# external_MCU.net
KiCad netlist of a schematic drawn in Altium Designer
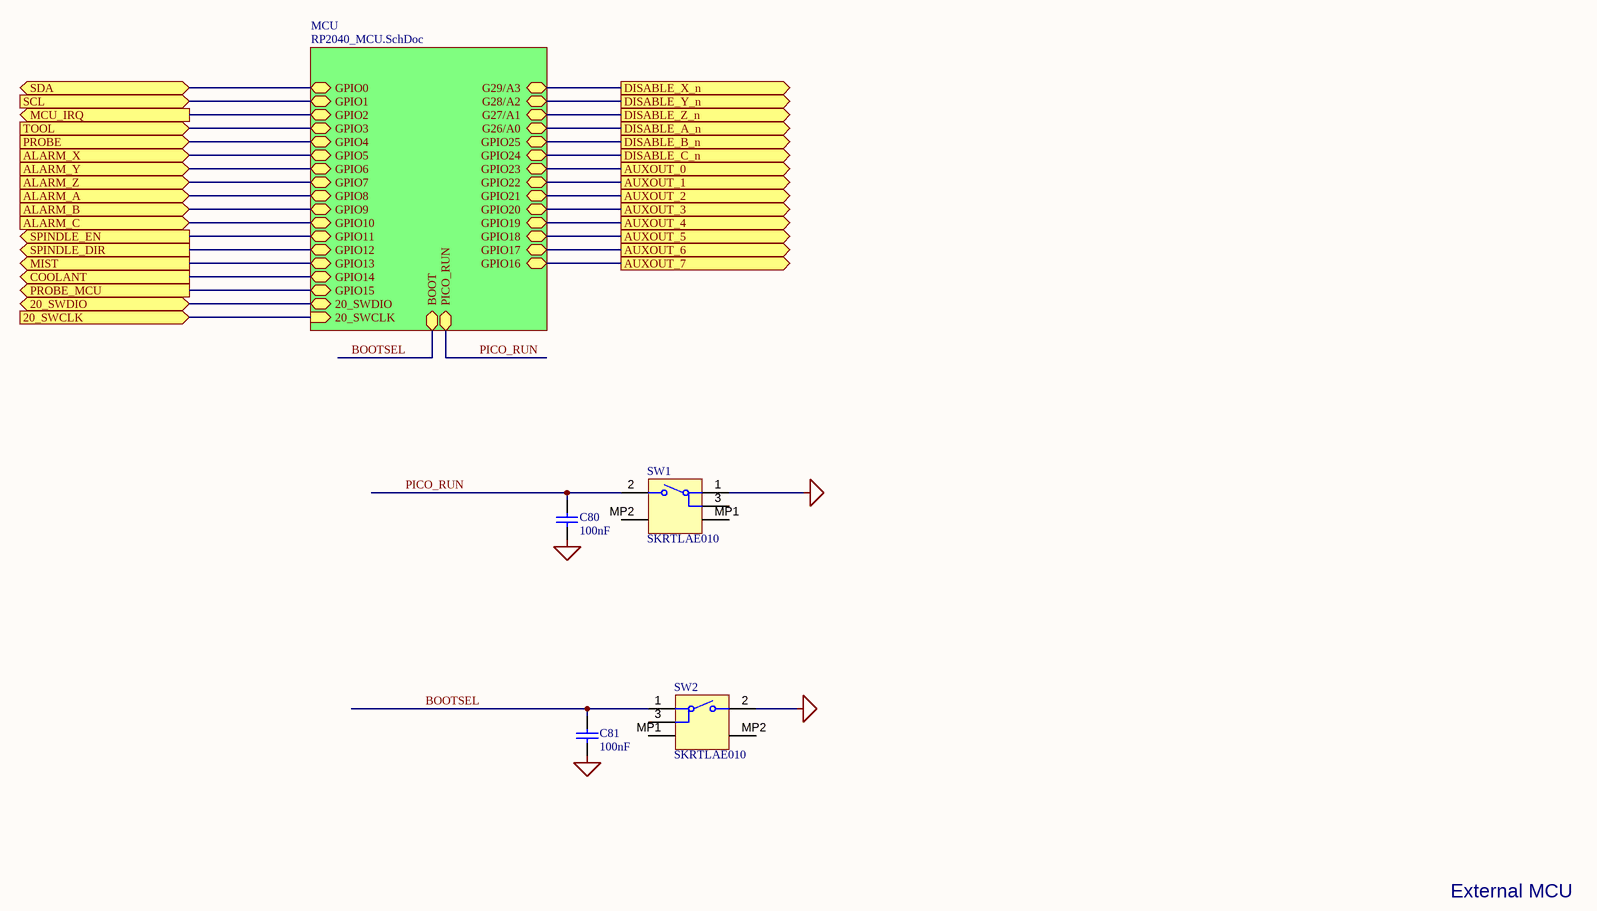
[diagram p0: external_MCU.SchDoc]

(export (version "E")
  (design (tool "Eeschema 10.0.6"))
  (components
    (comp (ref "C80")
      (value "100nF")
      (footprint "0402_C")
      (description "Chip capacitors")
      (fields
        (field (name "MANUFACTURER") "Samsung Electro-Mechanics")
        (field (name "PARTNUMBER") "CL05B104KO5NNNC")
      )
      (libsource (lib "Cap") (part "0402 100nF (104) 10% 16V"))
    )
    (comp (ref "C81")
      (value "100nF")
      (footprint "0402_C")
      (description "Chip capacitors")
      (fields
        (field (name "MANUFACTURER") "Samsung Electro-Mechanics")
        (field (name "PARTNUMBER") "CL05B104KO5NNNC")
      )
      (libsource (lib "Cap") (part "0402 100nF (104) 10% 16V"))
    )
    (comp (ref "SW1")
      (value "SKRTLAE010")
      (footprint "ALPS-SKRTLAE010_V")
      (description "Side Push Type, 250 V, -40 to 90 degC, 3-Pin SMD, RoHS, Tape and Reel")
      (fields (field (name "MANUFACTURER") "ALPS"))
      (libsource (lib "") (part "SW_SPST-3_A_1"))
    )
    (comp (ref "SW2")
      (value "SKRTLAE010")
      (footprint "ALPS-SKRTLAE010_V")
      (description "Side Push Type, 250 V, -40 to 90 degC, 3-Pin SMD, RoHS, Tape and Reel")
      (fields (field (name "MANUFACTURER") "ALPS"))
      (libsource (lib "Altium Content Vault") (part "SW_SPST-3_A"))
    )
  )
  (nets
    (net (code "17") (name "/BOOTSEL") (class "Default")
      (node (ref "C81") (pin "2") (pinfunction "2_2") (pintype "passive"))
      (node (ref "SW2") (pin "1") (pinfunction "1_1") (pintype "passive"))
    )
    (net (code "27") (name "/PICO_RUN") (class "Default")
      (node (ref "C80") (pin "2") (pinfunction "2_2") (pintype "passive"))
      (node (ref "SW1") (pin "2") (pinfunction "2_2") (pintype "passive"))
    )
    (net (code "35") (name "MCU_GND") (class "Default")
      (node (ref "C80") (pin "1") (pinfunction "1_1") (pintype "passive"))
      (node (ref "C81") (pin "1") (pinfunction "1_1") (pintype "passive"))
      (node (ref "SW1") (pin "1") (pinfunction "1_1") (pintype "passive"))
      (node (ref "SW2") (pin "2") (pinfunction "2_2") (pintype "passive"))
    )
    (net (code "36") (name "unconnected-(SW1-Pad3)") (class "Default")
      (node (ref "SW1") (pin "3") (pinfunction "3_3") (pintype "passive"))
    )
    (net (code "37") (name "unconnected-(SW1-PadMP1)") (class "Default")
      (node (ref "SW1") (pin "MP1") (pinfunction "MP1_MP1") (pintype "passive"))
    )
    (net (code "38") (name "unconnected-(SW1-PadMP2)") (class "Default")
      (node (ref "SW1") (pin "MP2") (pinfunction "MP2_MP2") (pintype "passive"))
    )
    (net (code "39") (name "unconnected-(SW2-Pad3)") (class "Default")
      (node (ref "SW2") (pin "3") (pinfunction "3_3") (pintype "passive"))
    )
    (net (code "40") (name "unconnected-(SW2-PadMP1)") (class "Default")
      (node (ref "SW2") (pin "MP1") (pinfunction "MP1_MP1") (pintype "passive"))
    )
    (net (code "41") (name "unconnected-(SW2-PadMP2)") (class "Default")
      (node (ref "SW2") (pin "MP2") (pinfunction "MP2_MP2") (pintype "passive"))
    )
  )
)
